# 2_SIM_Interface.net
KiCad netlist of a schematic drawn in Altium Designer
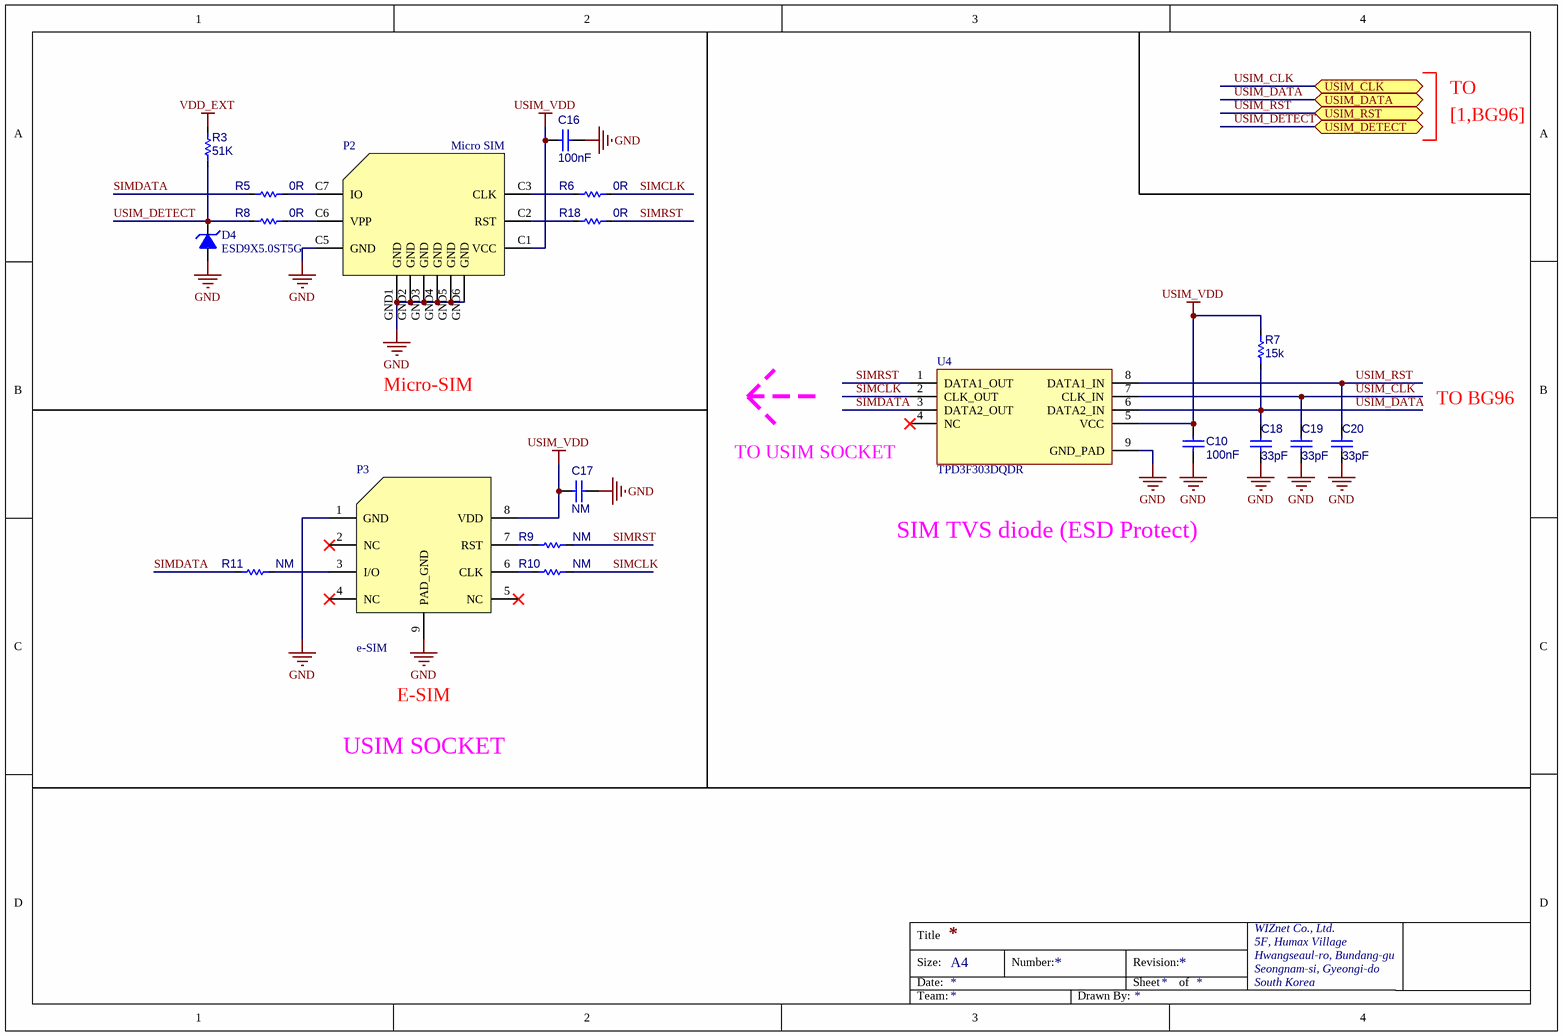
[diagram p0: 2.SIM Interface.SchDoc]

(export (version "E")
  (design (tool "Eeschema 10.0.6"))
  (components
    (comp (ref "C10")
      (value "100nF")
      (footprint "CAP-0402")
      (description "Ceramic CAP 0402(1005)")
      (libsource (lib "Scott_lib") (part "CAP-0402"))
    )
    (comp (ref "C16")
      (value "100nF")
      (footprint "CAP-0402")
      (description "Ceramic CAP 0402(1005)")
      (libsource (lib "Scott_lib") (part "CAP-0402"))
    )
    (comp (ref "C17")
      (value "NM")
      (footprint "CAP-0402")
      (description "Ceramic CAP 0402(1005)")
      (libsource (lib "Scott_lib") (part "CAP-0402"))
    )
    (comp (ref "C18")
      (value "33pF")
      (footprint "CAP-0402")
      (description "Ceramic CAP 0402(1005)")
      (libsource (lib "Scott_lib") (part "CAP-0402"))
    )
    (comp (ref "C19")
      (value "33pF")
      (footprint "CAP-0402")
      (description "Ceramic CAP 0402(1005)")
      (libsource (lib "Scott_lib") (part "CAP-0402"))
    )
    (comp (ref "C20")
      (value "33pF")
      (footprint "CAP-0402")
      (description "Ceramic CAP 0402(1005)")
      (libsource (lib "Scott_lib") (part "CAP-0402"))
    )
    (comp (ref "D4")
      (value "ESD9X5.0ST5G")
      (footprint "SOD-923(1-C,2-A)")
      (description "Uni-directional TVS diode")
      (libsource (lib "Edward") (part "ESD9X5.0ST5G"))
    )
    (comp (ref "P2")
      (value "Micro SIM")
      (footprint "MOLEX-SD-78646-001")
      (description "Micro SIM SMT 1.45mm Push/Pull")
      (libsource (lib "Quectel_IF_Board") (part "Micro SIM"))
    )
    (comp (ref "P3")
      (value "e-SIM")
      (footprint "MFF2(1.27/5x6)")
      (libsource (lib "Quectel_IF_Board") (part "e-SIM"))
    )
    (comp (ref "R3")
      (value "51K")
      (footprint "RES-0402")
      (description "RES-0402")
      (libsource (lib "Scott_lib") (part "RES-0402"))
    )
    (comp (ref "R5")
      (value "0R")
      (footprint "RES-0402")
      (description "RES-0402")
      (libsource (lib "Scott_lib") (part "RES-0402"))
    )
    (comp (ref "R6")
      (value "0R")
      (footprint "RES-0402")
      (description "RES-0402")
      (libsource (lib "Scott_lib") (part "RES-0402"))
    )
    (comp (ref "R7")
      (value "15k")
      (footprint "RES-0402")
      (description "RES-0402")
      (libsource (lib "Scott_lib") (part "RES-0402"))
    )
    (comp (ref "R8")
      (value "0R")
      (footprint "RES-0402")
      (description "RES-0402")
      (libsource (lib "Scott_lib") (part "RES-0402"))
    )
    (comp (ref "R9")
      (value "NM")
      (footprint "RES-0402")
      (description "RES-0402")
      (libsource (lib "Scott_lib") (part "RES-0402"))
    )
    (comp (ref "R10")
      (value "NM")
      (footprint "RES-0402")
      (description "RES-0402")
      (libsource (lib "Scott_lib") (part "RES-0402"))
    )
    (comp (ref "R11")
      (value "NM")
      (footprint "RES-0402")
      (description "RES-0402")
      (libsource (lib "Scott_lib") (part "RES-0402"))
    )
    (comp (ref "R18")
      (value "0R")
      (footprint "RES-0402")
      (description "RES-0402")
      (libsource (lib "Scott_lib") (part "RES-0402"))
    )
    (comp (ref "U4")
      (value "TPD3F303DQDR")
      (footprint "PWSON08(0.4/1.45X1.8)")
      (description "ESD Protection SIM")
      (libsource (lib "Quectel_IF_Board") (part "TPD3F303DQDR"))
    )
  )
  (nets
    (net (code "1") (name "/SIMCLK") (class "Default")
      (node (ref "R10") (pin "1") (pinfunction "1_1") (pintype "passive"))
      (node (ref "R6") (pin "1") (pinfunction "1_1") (pintype "passive"))
      (node (ref "U4") (pin "2") (pinfunction "CLK_OUT_2") (pintype "passive"))
    )
    (net (code "2") (name "/SIMDATA") (class "Default")
      (node (ref "R11") (pin "2") (pinfunction "2_2") (pintype "passive"))
      (node (ref "R5") (pin "2") (pinfunction "2_2") (pintype "passive"))
      (node (ref "U4") (pin "3") (pinfunction "DATA2_OUT_3") (pintype "passive"))
    )
    (net (code "3") (name "/SIMRST") (class "Default")
      (node (ref "R18") (pin "1") (pinfunction "1_1") (pintype "passive"))
      (node (ref "R9") (pin "1") (pinfunction "1_1") (pintype "passive"))
      (node (ref "U4") (pin "1") (pinfunction "DATA1_OUT_1") (pintype "passive"))
    )
    (net (code "4") (name "/USIM_CLK") (class "Default")
      (node (ref "C19") (pin "2") (pinfunction "2_2") (pintype "passive"))
      (node (ref "U4") (pin "7") (pinfunction "CLK_IN_7") (pintype "passive"))
    )
    (net (code "5") (name "/USIM_DATA") (class "Default")
      (node (ref "C18") (pin "2") (pinfunction "2_2") (pintype "passive"))
      (node (ref "R7") (pin "2") (pinfunction "2_2") (pintype "passive"))
      (node (ref "U4") (pin "6") (pinfunction "DATA2_IN_6") (pintype "passive"))
    )
    (net (code "6") (name "/USIM_DETECT") (class "Default")
      (node (ref "D4") (pin "1") (pinfunction "1_1") (pintype "passive"))
      (node (ref "R3") (pin "2") (pinfunction "2_2") (pintype "passive"))
      (node (ref "R8") (pin "2") (pinfunction "2_2") (pintype "passive"))
    )
    (net (code "7") (name "/USIM_RST") (class "Default")
      (node (ref "C20") (pin "2") (pinfunction "2_2") (pintype "passive"))
      (node (ref "U4") (pin "8") (pinfunction "DATA1_IN_8") (pintype "passive"))
    )
    (net (code "8") (name "GND") (class "Default")
      (node (ref "C10") (pin "2") (pinfunction "2_2") (pintype "passive"))
      (node (ref "C16") (pin "1") (pinfunction "1_1") (pintype "passive"))
      (node (ref "C17") (pin "1") (pinfunction "1_1") (pintype "passive"))
      (node (ref "C18") (pin "1") (pinfunction "1_1") (pintype "passive"))
      (node (ref "C19") (pin "1") (pinfunction "1_1") (pintype "passive"))
      (node (ref "C20") (pin "1") (pinfunction "1_1") (pintype "passive"))
      (node (ref "D4") (pin "2") (pinfunction "2_2") (pintype "passive"))
      (node (ref "P2") (pin "C5") (pinfunction "GND_C5") (pintype "passive"))
      (node (ref "P2") (pin "GND1") (pinfunction "GND_GND1") (pintype "passive"))
      (node (ref "P2") (pin "GND2") (pinfunction "GND_GND2") (pintype "passive"))
      (node (ref "P2") (pin "GND3") (pinfunction "GND_GND3") (pintype "passive"))
      (node (ref "P2") (pin "GND4") (pinfunction "GND_GND4") (pintype "passive"))
      (node (ref "P2") (pin "GND5") (pinfunction "GND_GND5") (pintype "passive"))
      (node (ref "P2") (pin "GND6") (pinfunction "GND_GND6") (pintype "passive"))
      (node (ref "P3") (pin "1") (pinfunction "GND_1") (pintype "passive"))
      (node (ref "P3") (pin "9") (pinfunction "PAD_GND_9") (pintype "passive"))
      (node (ref "U4") (pin "9") (pinfunction "GND_PAD_9") (pintype "passive"))
    )
    (net (code "9") (name "Net-(P2-CLK)") (class "Default")
      (node (ref "P2") (pin "C3") (pinfunction "CLK_C3") (pintype "passive"))
      (node (ref "R6") (pin "2") (pinfunction "2_2") (pintype "passive"))
    )
    (net (code "10") (name "Net-(P2-IO)") (class "Default")
      (node (ref "P2") (pin "C7") (pinfunction "IO_C7") (pintype "passive"))
      (node (ref "R5") (pin "1") (pinfunction "1_1") (pintype "passive"))
    )
    (net (code "11") (name "Net-(P2-RST)") (class "Default")
      (node (ref "P2") (pin "C2") (pinfunction "RST_C2") (pintype "passive"))
      (node (ref "R18") (pin "2") (pinfunction "2_2") (pintype "passive"))
    )
    (net (code "12") (name "Net-(P2-VPP)") (class "Default")
      (node (ref "P2") (pin "C6") (pinfunction "VPP_C6") (pintype "passive"))
      (node (ref "R8") (pin "1") (pinfunction "1_1") (pintype "passive"))
    )
    (net (code "13") (name "Net-(P3-CLK)") (class "Default")
      (node (ref "P3") (pin "6") (pinfunction "CLK_6") (pintype "passive"))
      (node (ref "R10") (pin "2") (pinfunction "2_2") (pintype "passive"))
    )
    (net (code "14") (name "Net-(P3-I{slash}O)") (class "Default")
      (node (ref "P3") (pin "3") (pinfunction "I/O_3") (pintype "passive"))
      (node (ref "R11") (pin "1") (pinfunction "1_1") (pintype "passive"))
    )
    (net (code "15") (name "Net-(P3-RST)") (class "Default")
      (node (ref "P3") (pin "7") (pinfunction "RST_7") (pintype "passive"))
      (node (ref "R9") (pin "2") (pinfunction "2_2") (pintype "passive"))
    )
    (net (code "16") (name "USIM_VDD") (class "Default")
      (node (ref "C10") (pin "1") (pinfunction "1_1") (pintype "passive"))
      (node (ref "C16") (pin "2") (pinfunction "2_2") (pintype "passive"))
      (node (ref "C17") (pin "2") (pinfunction "2_2") (pintype "passive"))
      (node (ref "P2") (pin "C1") (pinfunction "VCC_C1") (pintype "passive"))
      (node (ref "P3") (pin "8") (pinfunction "VDD_8") (pintype "passive"))
      (node (ref "R7") (pin "1") (pinfunction "1_1") (pintype "passive"))
      (node (ref "U4") (pin "5") (pinfunction "VCC_5") (pintype "passive"))
    )
    (net (code "17") (name "VDD_EXT") (class "Default")
      (node (ref "R3") (pin "1") (pinfunction "1_1") (pintype "passive"))
    )
    (net (code "18") (name "unconnected-(P3-NC-Pad2)") (class "Default")
      (node (ref "P3") (pin "2") (pinfunction "NC_2") (pintype "passive+no_connect"))
    )
    (net (code "19") (name "unconnected-(P3-NC-Pad4)") (class "Default")
      (node (ref "P3") (pin "4") (pinfunction "NC_4") (pintype "passive+no_connect"))
    )
    (net (code "20") (name "unconnected-(P3-NC-Pad5)") (class "Default")
      (node (ref "P3") (pin "5") (pinfunction "NC_5") (pintype "passive+no_connect"))
    )
    (net (code "21") (name "unconnected-(U4-NC-Pad4)") (class "Default")
      (node (ref "U4") (pin "4") (pinfunction "NC_4") (pintype "passive+no_connect"))
    )
  )
)
